# Yaris_speed_door_lock.net
KiCad netlist of a schematic drawn in EAGLE
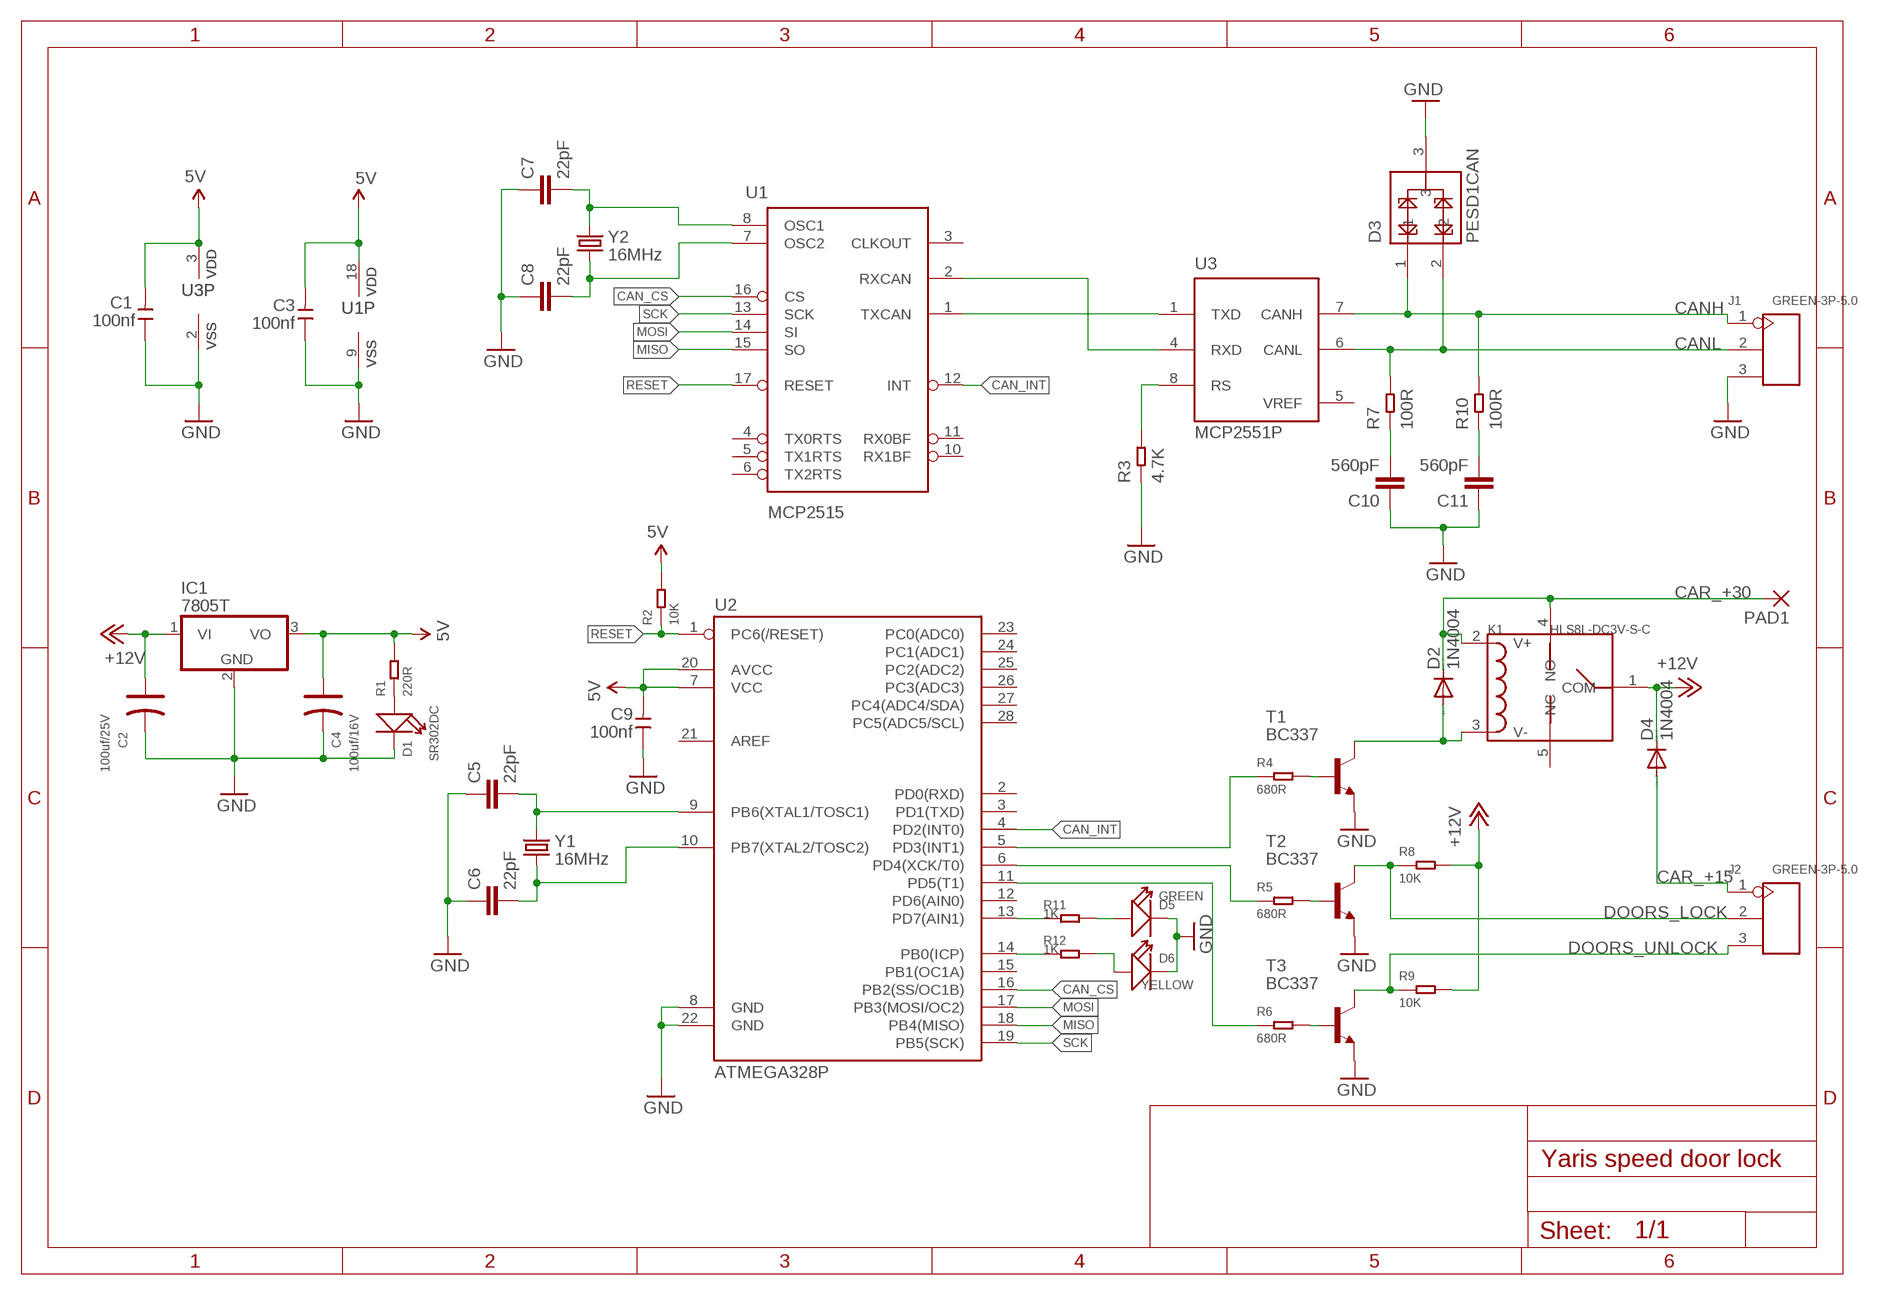
[diagram p0: schematic, sheet 1]

(export (version "E")
  (design (tool "Eeschema 10.0.6"))
  (components
    (comp (ref "C1")
      (value "100nf")
      (footprint "eagle-import:CERAMIC-2.54")
      (fields (field (name "MPN") "CC1-F5SL2A101KSPW"))
      (libsource (lib "eagle-import") (part "DIP-CERAMIC-DISC-100NF-50V-Y5V(D5.0MM)"))
    )
    (comp (ref "C2")
      (value "100uf/25V")
      (footprint "eagle-import:PC-D5.3MM")
      (fields (field (name "MPN") "KS 100uF/16V"))
      (libsource (lib "eagle-import") (part "DIP-ALUMINUM-100UF-16V(D5-H7MM)"))
    )
    (comp (ref "C3")
      (value "100nf")
      (footprint "eagle-import:CERAMIC-2.54")
      (fields (field (name "MPN") "CC1-F5SL2A101KSPW"))
      (libsource (lib "eagle-import") (part "DIP-CERAMIC-DISC-100NF-50V-Y5V(D5.0MM)"))
    )
    (comp (ref "C4")
      (value "100uf/16V")
      (footprint "eagle-import:PC-D5.3MM")
      (fields (field (name "MPN") "KS 100uF/16V"))
      (libsource (lib "eagle-import") (part "DIP-ALUMINUM-100UF-16V(D5-H7MM)"))
    )
    (comp (ref "C5")
      (value "22pF")
      (footprint "eagle-import:CAP-PTH-2.54")
      (libsource (lib "eagle-import") (part "22PF-PTH-2.54MM-200V-5%"))
    )
    (comp (ref "C6")
      (value "22pF")
      (footprint "eagle-import:CAP-PTH-2.54")
      (libsource (lib "eagle-import") (part "22PF-PTH-2.54MM-200V-5%"))
    )
    (comp (ref "C7")
      (value "22pF")
      (footprint "eagle-import:CAP-PTH-2.54")
      (libsource (lib "eagle-import") (part "22PF-PTH-2.54MM-200V-5%"))
    )
    (comp (ref "C8")
      (value "22pF")
      (footprint "eagle-import:CAP-PTH-2.54")
      (libsource (lib "eagle-import") (part "22PF-PTH-2.54MM-200V-5%"))
    )
    (comp (ref "C9")
      (value "100nf")
      (footprint "eagle-import:CERAMIC-2.54")
      (fields (field (name "MPN") "CC1-F5SL2A101KSPW"))
      (libsource (lib "eagle-import") (part "DIP-CERAMIC-DISC-100NF-50V-Y5V(D5.0MM)"))
    )
    (comp (ref "C10")
      (value "560pF")
      (footprint "eagle-import:0603-CAP")
      (libsource (lib "eagle-import") (part "560PF-50V-5%(0603)"))
    )
    (comp (ref "C11")
      (value "560pF")
      (footprint "eagle-import:0603-CAP")
      (libsource (lib "eagle-import") (part "560PF-50V-5%(0603)"))
    )
    (comp (ref "D1")
      (value "SR302DC")
      (footprint "eagle-import:LED2-2.54-D3.0MM")
      (libsource (lib "eagle-import") (part "DIP-LED-RED-RED(2P-D3MM)"))
    )
    (comp (ref "D2")
      (value "1N4004")
      (footprint "eagle-import:DO41-10")
      (libsource (lib "eagle-import") (part "1N4004"))
    )
    (comp (ref "D3")
      (value "PESD1CAN")
      (footprint "eagle-import:SOT23-3")
      (libsource (lib "eagle-import") (part "PESD1CAN"))
    )
    (comp (ref "D4")
      (value "1N4004")
      (footprint "eagle-import:DO41-10")
      (libsource (lib "eagle-import") (part "1N4004"))
    )
    (comp (ref "D5")
      (value "GREEN")
      (footprint "eagle-import:LED2-2.54-D3.0MM")
      (fields (field (name "MPN") "CX-G302DC"))
      (libsource (lib "eagle-import") (part "DIP-LED-GREEN-GREEN(2P-D3MM)"))
    )
    (comp (ref "D6")
      (value "YELLOW")
      (footprint "eagle-import:LED2-2.54-D3.0MM")
      (fields (field (name "MPN") "CX-G302DC"))
      (libsource (lib "eagle-import") (part "DIP-LED-GREEN-GREEN(2P-D3MM)"))
    )
    (comp (ref "IC1")
      (value "7805T")
      (footprint "eagle-import:TO220H")
      (libsource (lib "eagle-import") (part "78T05"))
    )
    (comp (ref "J1")
      (value "GREEN-3P-5.0")
      (footprint "eagle-import:H3-5.0-15.5X8.0MM")
      (libsource (lib "eagle-import") (part "SCREW-TERMINAL-GREEN(3P-5.0)"))
    )
    (comp (ref "J2")
      (value "GREEN-3P-5.0")
      (footprint "eagle-import:H3-5.0-15.5X8.0MM")
      (libsource (lib "eagle-import") (part "SCREW-TERMINAL-GREEN(3P-5.0)"))
    )
    (comp (ref "K1")
      (value "HLS8L-DC3V-S-C")
      (footprint "eagle-import:REY5-19.0X15.0X15.0MM")
      (libsource (lib "eagle-import") (part "RELAY-HLS8L-DC3V-S-C(5P-19X15MM)"))
    )
    (comp (ref "PAD1")
      (value "2,15/1,0")
      (footprint "eagle-import:2,15_1,0")
      (libsource (lib "eagle-import") (part "2,15/1,0"))
    )
    (comp (ref "R1")
      (value "220R")
      (footprint "eagle-import:PR-D2.3XL6.5MM")
      (fields (field (name "MPN") "FHCFR-1/4W-221J"))
      (libsource (lib "eagle-import") (part "DIP-RES-220R-5%-1/4W(PR-D2.3XL6.5MM)"))
    )
    (comp (ref "R2")
      (value "10K")
      (footprint "eagle-import:PR-D2.3XL6.5MM")
      (fields (field (name "MPN") "FHCFR-1/4W-103J"))
      (libsource (lib "eagle-import") (part "DIP-RES-10K-5%-1/4W(PR-D2.3XL6.5MM)"))
    )
    (comp (ref "R3")
      (value "4.7K")
      (footprint "eagle-import:PR-D2.3XL6.5MM")
      (fields (field (name "MPN") "FHCFR-1/4W-472J"))
      (libsource (lib "eagle-import") (part "DIP-RES-4.7K-5%-1/4W(PR-D2.3XL6.5MM)"))
    )
    (comp (ref "R4")
      (value "680R")
      (footprint "eagle-import:PR-D2.3XL6.5MM")
      (fields (field (name "MPN") "FHCFR-1/4W-681J"))
      (libsource (lib "eagle-import") (part "DIP-RES-680R-5%-1/4W(PR-D2.3XL6.5MM)"))
    )
    (comp (ref "R5")
      (value "680R")
      (footprint "eagle-import:PR-D2.3XL6.5MM")
      (fields (field (name "MPN") "FHCFR-1/4W-681J"))
      (libsource (lib "eagle-import") (part "DIP-RES-680R-5%-1/4W(PR-D2.3XL6.5MM)"))
    )
    (comp (ref "R6")
      (value "680R")
      (footprint "eagle-import:PR-D2.3XL6.5MM")
      (fields (field (name "MPN") "FHCFR-1/4W-681J"))
      (libsource (lib "eagle-import") (part "DIP-RES-680R-5%-1/4W(PR-D2.3XL6.5MM)"))
    )
    (comp (ref "R7")
      (value "100R")
      (footprint "eagle-import:PR-D2.3XL6.5MM")
      (fields (field (name "MPN") "FHCFR-1/4W-101J"))
      (libsource (lib "eagle-import") (part "DIP-RES-100R-5%-1/4W(PR-D2.3XL6.5MM)"))
    )
    (comp (ref "R8")
      (value "10K")
      (footprint "eagle-import:PR-D2.3XL6.5MM")
      (fields (field (name "MPN") "FHCFR-1/4W-103J"))
      (libsource (lib "eagle-import") (part "DIP-RES-10K-5%-1/4W(PR-D2.3XL6.5MM)"))
    )
    (comp (ref "R9")
      (value "10K")
      (footprint "eagle-import:PR-D2.3XL6.5MM")
      (fields (field (name "MPN") "FHCFR-1/4W-103J"))
      (libsource (lib "eagle-import") (part "DIP-RES-10K-5%-1/4W(PR-D2.3XL6.5MM)"))
    )
    (comp (ref "R10")
      (value "100R")
      (footprint "eagle-import:PR-D2.3XL6.5MM")
      (fields (field (name "MPN") "FHCFR-1/4W-101J"))
      (libsource (lib "eagle-import") (part "DIP-RES-100R-5%-1/4W(PR-D2.3XL6.5MM)"))
    )
    (comp (ref "R11")
      (value "1K")
      (footprint "eagle-import:PR-D2.3XL6.5MM")
      (fields (field (name "MPN") "FHCFR-1/4W-102J"))
      (libsource (lib "eagle-import") (part "DIP-RES-1K-5%-1/4W(PR-D2.3XL6.5MM)"))
    )
    (comp (ref "R12")
      (value "1K")
      (footprint "eagle-import:PR-D2.3XL6.5MM")
      (fields (field (name "MPN") "FHCFR-1/4W-102J"))
      (libsource (lib "eagle-import") (part "DIP-RES-1K-5%-1/4W(PR-D2.3XL6.5MM)"))
    )
    (comp (ref "T1")
      (value "BC337")
      (footprint "eagle-import:TO92")
      (libsource (lib "eagle-import") (part "BC337"))
    )
    (comp (ref "T2")
      (value "BC337")
      (footprint "eagle-import:TO92")
      (libsource (lib "eagle-import") (part "BC337"))
    )
    (comp (ref "T3")
      (value "BC337")
      (footprint "eagle-import:TO92")
      (libsource (lib "eagle-import") (part "BC337"))
    )
    (comp (ref "U1")
      (value "MCP2515")
      (footprint "eagle-import:SO-18W")
      (libsource (lib "eagle-import") (part "MCP2510SO"))
    )
    (comp (ref "U2")
      (value "ATMEGA328P")
      (footprint "eagle-import:DIP28")
      (libsource (lib "eagle-import") (part "ATMEGA328P_PDIP"))
    )
    (comp (ref "U3")
      (value "MCP2551P")
      (footprint "eagle-import:DIL8")
      (libsource (lib "eagle-import") (part "MCP2551P"))
    )
    (comp (ref "Y1")
      (value "16MHz")
      (footprint "eagle-import:HC49US")
      (libsource (lib "eagle-import") (part "CRYSTALHC49US"))
    )
    (comp (ref "Y2")
      (value "16MHz")
      (footprint "eagle-import:HC49US")
      (libsource (lib "eagle-import") (part "CRYSTALHC49US"))
    )
  )
  (nets
    (net (code "1") (name "+12V") (class "Default")
      (node (ref "C2") (pin "+") (pinfunction "+_+") (pintype "passive"))
      (node (ref "D4") (pin "C") (pinfunction "C_C") (pintype "passive"))
      (node (ref "IC1") (pin "1") (pinfunction "VI_1") (pintype "input"))
      (node (ref "K1") (pin "1") (pinfunction "COM_1") (pintype "bidirectional"))
      (node (ref "R8") (pin "2") (pinfunction "2_2") (pintype "passive"))
      (node (ref "R9") (pin "2") (pinfunction "2_2") (pintype "passive"))
    )
    (net (code "2") (name "/CANH") (class "Default")
      (node (ref "D3") (pin "1") (pinfunction "1_1") (pintype "bidirectional"))
      (node (ref "J1") (pin "1") (pinfunction "P$1_1") (pintype "bidirectional"))
      (node (ref "R10") (pin "2") (pinfunction "2_2") (pintype "passive"))
      (node (ref "U3") (pin "7") (pinfunction "CANH_7") (pintype "bidirectional"))
    )
    (net (code "3") (name "/CANL") (class "Default")
      (node (ref "D3") (pin "2") (pinfunction "2_2") (pintype "bidirectional"))
      (node (ref "J1") (pin "2") (pinfunction "P$2_2") (pintype "bidirectional"))
      (node (ref "R7") (pin "2") (pinfunction "2_2") (pintype "passive"))
      (node (ref "U3") (pin "6") (pinfunction "CANL_6") (pintype "bidirectional"))
    )
    (net (code "4") (name "/CAR_+15") (class "Default")
      (node (ref "D4") (pin "A") (pinfunction "A_A") (pintype "passive"))
      (node (ref "J2") (pin "1") (pinfunction "P$1_1") (pintype "bidirectional"))
    )
    (net (code "5") (name "/CAR_+30") (class "Default")
      (node (ref "D2") (pin "C") (pinfunction "C_C") (pintype "passive"))
      (node (ref "K1") (pin "2") (pinfunction "V+_2") (pintype "bidirectional"))
      (node (ref "K1") (pin "4") (pinfunction "NO_4") (pintype "bidirectional"))
      (node (ref "PAD1") (pin "1") (pinfunction "P_1") (pintype "passive"))
    )
    (net (code "6") (name "/DOORS_LOCK") (class "Default")
      (node (ref "J2") (pin "2") (pinfunction "P$2_2") (pintype "bidirectional"))
      (node (ref "R8") (pin "1") (pinfunction "1_1") (pintype "passive"))
      (node (ref "T2") (pin "3") (pinfunction "C_3") (pintype "passive"))
    )
    (net (code "7") (name "/DOORS_UNLOCK") (class "Default")
      (node (ref "J2") (pin "3") (pinfunction "P$3_3") (pintype "bidirectional"))
      (node (ref "R9") (pin "1") (pinfunction "1_1") (pintype "passive"))
      (node (ref "T3") (pin "3") (pinfunction "C_3") (pintype "passive"))
    )
    (net (code "8") (name "/VREF") (class "Default")
      (node (ref "U3") (pin "5") (pinfunction "VREF_5") (pintype "power_in"))
    )
    (net (code "9") (name "5V") (class "Default")
      (node (ref "C1") (pin "2") (pinfunction "2_2") (pintype "passive"))
      (node (ref "C3") (pin "2") (pinfunction "2_2") (pintype "passive"))
      (node (ref "C4") (pin "+") (pinfunction "+_+") (pintype "passive"))
      (node (ref "C9") (pin "2") (pinfunction "2_2") (pintype "passive"))
      (node (ref "IC1") (pin "3") (pinfunction "VO_3") (pintype "passive"))
      (node (ref "R1") (pin "2") (pinfunction "2_2") (pintype "passive"))
      (node (ref "R2") (pin "2") (pinfunction "2_2") (pintype "passive"))
      (node (ref "U1") (pin "18") (pinfunction "VDD_18") (pintype "power_in"))
      (node (ref "U2") (pin "20") (pinfunction "AVCC_20") (pintype "bidirectional"))
      (node (ref "U2") (pin "7") (pinfunction "VCC_7") (pintype "bidirectional"))
      (node (ref "U3") (pin "3") (pinfunction "VDD_3") (pintype "power_in"))
    )
    (net (code "10") (name "CAN_CS") (class "Default")
      (node (ref "U1") (pin "16") (pinfunction "CS_16") (pintype "input"))
      (node (ref "U2") (pin "16") (pinfunction "PB2(SS/OC1B)_16") (pintype "bidirectional"))
    )
    (net (code "11") (name "CAN_INT") (class "Default")
      (node (ref "U1") (pin "12") (pinfunction "INT_12") (pintype "output"))
      (node (ref "U2") (pin "4") (pinfunction "PD2(INT0)_4") (pintype "bidirectional"))
    )
    (net (code "12") (name "GND") (class "Default")
      (node (ref "C1") (pin "1") (pinfunction "1_1") (pintype "passive"))
      (node (ref "C10") (pin "1") (pinfunction "1_1") (pintype "passive"))
      (node (ref "C11") (pin "1") (pinfunction "1_1") (pintype "passive"))
      (node (ref "C2") (pin "-") (pinfunction "-_-") (pintype "passive"))
      (node (ref "C3") (pin "1") (pinfunction "1_1") (pintype "passive"))
      (node (ref "C4") (pin "-") (pinfunction "-_-") (pintype "passive"))
      (node (ref "C5") (pin "1") (pinfunction "1_1") (pintype "passive"))
      (node (ref "C6") (pin "1") (pinfunction "1_1") (pintype "passive"))
      (node (ref "C7") (pin "1") (pinfunction "1_1") (pintype "passive"))
      (node (ref "C8") (pin "1") (pinfunction "1_1") (pintype "passive"))
      (node (ref "C9") (pin "1") (pinfunction "1_1") (pintype "passive"))
      (node (ref "D1") (pin "K") (pinfunction "-_K") (pintype "passive"))
      (node (ref "D3") (pin "3") (pinfunction "3_3") (pintype "bidirectional"))
      (node (ref "D5") (pin "K") (pinfunction "-_K") (pintype "passive"))
      (node (ref "D6") (pin "K") (pinfunction "-_K") (pintype "passive"))
      (node (ref "IC1") (pin "2") (pinfunction "GND_2") (pintype "passive"))
      (node (ref "J1") (pin "3") (pinfunction "P$3_3") (pintype "bidirectional"))
      (node (ref "R3") (pin "1") (pinfunction "1_1") (pintype "passive"))
      (node (ref "T1") (pin "1") (pinfunction "E_1") (pintype "passive"))
      (node (ref "T2") (pin "1") (pinfunction "E_1") (pintype "passive"))
      (node (ref "T3") (pin "1") (pinfunction "E_1") (pintype "passive"))
      (node (ref "U1") (pin "9") (pinfunction "VSS_9") (pintype "power_in"))
      (node (ref "U2") (pin "22") (pinfunction "GND_22") (pintype "bidirectional"))
      (node (ref "U2") (pin "8") (pinfunction "GND_8") (pintype "bidirectional"))
      (node (ref "U3") (pin "2") (pinfunction "VSS_2") (pintype "power_in"))
    )
    (net (code "13") (name "MISO") (class "Default")
      (node (ref "U1") (pin "15") (pinfunction "SO_15") (pintype "output"))
      (node (ref "U2") (pin "18") (pinfunction "PB4(MISO)_18") (pintype "bidirectional"))
    )
    (net (code "14") (name "MOSI") (class "Default")
      (node (ref "U1") (pin "14") (pinfunction "SI_14") (pintype "input"))
      (node (ref "U2") (pin "17") (pinfunction "PB3(MOSI/OC2)_17") (pintype "bidirectional"))
    )
    (net (code "15") (name "Net-(C10-Pad2)") (class "Default")
      (node (ref "C10") (pin "2") (pinfunction "2_2") (pintype "passive"))
      (node (ref "R7") (pin "1") (pinfunction "1_1") (pintype "passive"))
    )
    (net (code "16") (name "Net-(C11-Pad2)") (class "Default")
      (node (ref "C11") (pin "2") (pinfunction "2_2") (pintype "passive"))
      (node (ref "R10") (pin "1") (pinfunction "1_1") (pintype "passive"))
    )
    (net (code "17") (name "Net-(D1-+)") (class "Default")
      (node (ref "D1") (pin "A") (pinfunction "+_A") (pintype "passive"))
      (node (ref "R1") (pin "1") (pinfunction "1_1") (pintype "passive"))
    )
    (net (code "18") (name "Net-(D5-+)") (class "Default")
      (node (ref "D5") (pin "A") (pinfunction "+_A") (pintype "passive"))
      (node (ref "R11") (pin "2") (pinfunction "2_2") (pintype "passive"))
    )
    (net (code "19") (name "Net-(D6-+)") (class "Default")
      (node (ref "D6") (pin "A") (pinfunction "+_A") (pintype "passive"))
      (node (ref "R12") (pin "2") (pinfunction "2_2") (pintype "passive"))
    )
    (net (code "20") (name "Net-(K1-V-)") (class "Default")
      (node (ref "D2") (pin "A") (pinfunction "A_A") (pintype "passive"))
      (node (ref "K1") (pin "3") (pinfunction "V-_3") (pintype "bidirectional"))
      (node (ref "T1") (pin "3") (pinfunction "C_3") (pintype "passive"))
    )
    (net (code "21") (name "Net-(T1-B)") (class "Default")
      (node (ref "R4") (pin "2") (pinfunction "2_2") (pintype "passive"))
      (node (ref "T1") (pin "2") (pinfunction "B_2") (pintype "passive"))
    )
    (net (code "22") (name "Net-(T2-B)") (class "Default")
      (node (ref "R5") (pin "2") (pinfunction "2_2") (pintype "passive"))
      (node (ref "T2") (pin "2") (pinfunction "B_2") (pintype "passive"))
    )
    (net (code "23") (name "Net-(T3-B)") (class "Default")
      (node (ref "R6") (pin "2") (pinfunction "2_2") (pintype "passive"))
      (node (ref "T3") (pin "2") (pinfunction "B_2") (pintype "passive"))
    )
    (net (code "24") (name "Net-(U1A-OSC1)") (class "Default")
      (node (ref "C7") (pin "2") (pinfunction "2_2") (pintype "passive"))
      (node (ref "U1") (pin "8") (pinfunction "OSC1_8") (pintype "input"))
      (node (ref "Y2") (pin "2") (pinfunction "2_2") (pintype "passive"))
    )
    (net (code "25") (name "Net-(U1A-OSC2)") (class "Default")
      (node (ref "C8") (pin "2") (pinfunction "2_2") (pintype "passive"))
      (node (ref "U1") (pin "7") (pinfunction "OSC2_7") (pintype "output"))
      (node (ref "Y2") (pin "1") (pinfunction "1_1") (pintype "passive"))
    )
    (net (code "26") (name "Net-(U1A-RXCAN)") (class "Default")
      (node (ref "U1") (pin "2") (pinfunction "RXCAN_2") (pintype "input"))
      (node (ref "U3") (pin "4") (pinfunction "RXD_4") (pintype "output"))
    )
    (net (code "27") (name "Net-(U1A-TXCAN)") (class "Default")
      (node (ref "U1") (pin "1") (pinfunction "TXCAN_1") (pintype "output"))
      (node (ref "U3") (pin "1") (pinfunction "TXD_1") (pintype "input"))
    )
    (net (code "28") (name "Net-(U2-PB0(ICP))") (class "Default")
      (node (ref "R12") (pin "1") (pinfunction "1_1") (pintype "passive"))
      (node (ref "U2") (pin "14") (pinfunction "PB0(ICP)_14") (pintype "bidirectional"))
    )
    (net (code "29") (name "Net-(U2-PB6(XTAL1{slash}TOSC1))") (class "Default")
      (node (ref "C5") (pin "2") (pinfunction "2_2") (pintype "passive"))
      (node (ref "U2") (pin "9") (pinfunction "PB6(XTAL1/TOSC1)_9") (pintype "bidirectional"))
      (node (ref "Y1") (pin "2") (pinfunction "2_2") (pintype "passive"))
    )
    (net (code "30") (name "Net-(U2-PB7(XTAL2{slash}TOSC2))") (class "Default")
      (node (ref "C6") (pin "2") (pinfunction "2_2") (pintype "passive"))
      (node (ref "U2") (pin "10") (pinfunction "PB7(XTAL2/TOSC2)_10") (pintype "bidirectional"))
      (node (ref "Y1") (pin "1") (pinfunction "1_1") (pintype "passive"))
    )
    (net (code "31") (name "Net-(U2-PD3(INT1))") (class "Default")
      (node (ref "R4") (pin "1") (pinfunction "1_1") (pintype "passive"))
      (node (ref "U2") (pin "5") (pinfunction "PD3(INT1)_5") (pintype "bidirectional"))
    )
    (net (code "32") (name "Net-(U2-PD4(XCK{slash}T0))") (class "Default")
      (node (ref "R5") (pin "1") (pinfunction "1_1") (pintype "passive"))
      (node (ref "U2") (pin "6") (pinfunction "PD4(XCK/T0)_6") (pintype "bidirectional"))
    )
    (net (code "33") (name "Net-(U2-PD5(T1))") (class "Default")
      (node (ref "R6") (pin "1") (pinfunction "1_1") (pintype "passive"))
      (node (ref "U2") (pin "11") (pinfunction "PD5(T1)_11") (pintype "bidirectional"))
    )
    (net (code "34") (name "Net-(U2-PD7(AIN1))") (class "Default")
      (node (ref "R11") (pin "1") (pinfunction "1_1") (pintype "passive"))
      (node (ref "U2") (pin "13") (pinfunction "PD7(AIN1)_13") (pintype "bidirectional"))
    )
    (net (code "35") (name "Net-(U3A-RS)") (class "Default")
      (node (ref "R3") (pin "2") (pinfunction "2_2") (pintype "passive"))
      (node (ref "U3") (pin "8") (pinfunction "RS_8") (pintype "input"))
    )
    (net (code "36") (name "RESET") (class "Default")
      (node (ref "R2") (pin "1") (pinfunction "1_1") (pintype "passive"))
      (node (ref "U1") (pin "17") (pinfunction "RESET_17") (pintype "input"))
      (node (ref "U2") (pin "1") (pinfunction "PC6(/RESET)_1") (pintype "bidirectional"))
    )
    (net (code "37") (name "SCK") (class "Default")
      (node (ref "U1") (pin "13") (pinfunction "SCK_13") (pintype "input"))
      (node (ref "U2") (pin "19") (pinfunction "PB5(SCK)_19") (pintype "bidirectional"))
    )
    (net (code "38") (name "unconnected-(K1-NC-Pad5)") (class "Default")
      (node (ref "K1") (pin "5") (pinfunction "NC_5") (pintype "bidirectional"))
    )
    (net (code "39") (name "unconnected-(U1A-CLKOUT-Pad3)") (class "Default")
      (node (ref "U1") (pin "3") (pinfunction "CLKOUT_3") (pintype "output"))
    )
    (net (code "40") (name "unconnected-(U1A-RX0BF-Pad11)") (class "Default")
      (node (ref "U1") (pin "11") (pinfunction "RX0BF_11") (pintype "output"))
    )
    (net (code "41") (name "unconnected-(U1A-RX1BF-Pad10)") (class "Default")
      (node (ref "U1") (pin "10") (pinfunction "RX1BF_10") (pintype "output"))
    )
    (net (code "42") (name "unconnected-(U1A-TX0RTS-Pad4)") (class "Default")
      (node (ref "U1") (pin "4") (pinfunction "TX0RTS_4") (pintype "input"))
    )
    (net (code "43") (name "unconnected-(U1A-TX1RTS-Pad5)") (class "Default")
      (node (ref "U1") (pin "5") (pinfunction "TX1RTS_5") (pintype "input"))
    )
    (net (code "44") (name "unconnected-(U1A-TX2RTS-Pad6)") (class "Default")
      (node (ref "U1") (pin "6") (pinfunction "TX2RTS_6") (pintype "input"))
    )
    (net (code "45") (name "unconnected-(U2-AREF-Pad21)") (class "Default")
      (node (ref "U2") (pin "21") (pinfunction "AREF_21") (pintype "bidirectional"))
    )
    (net (code "46") (name "unconnected-(U2-PB1(OC1A)-Pad15)") (class "Default")
      (node (ref "U2") (pin "15") (pinfunction "PB1(OC1A)_15") (pintype "bidirectional"))
    )
    (net (code "47") (name "unconnected-(U2-PC0(ADC0)-Pad23)") (class "Default")
      (node (ref "U2") (pin "23") (pinfunction "PC0(ADC0)_23") (pintype "bidirectional"))
    )
    (net (code "48") (name "unconnected-(U2-PC1(ADC1)-Pad24)") (class "Default")
      (node (ref "U2") (pin "24") (pinfunction "PC1(ADC1)_24") (pintype "bidirectional"))
    )
    (net (code "49") (name "unconnected-(U2-PC2(ADC2)-Pad25)") (class "Default")
      (node (ref "U2") (pin "25") (pinfunction "PC2(ADC2)_25") (pintype "bidirectional"))
    )
    (net (code "50") (name "unconnected-(U2-PC3(ADC3)-Pad26)") (class "Default")
      (node (ref "U2") (pin "26") (pinfunction "PC3(ADC3)_26") (pintype "bidirectional"))
    )
    (net (code "51") (name "unconnected-(U2-PC4(ADC4{slash}SDA)-Pad27)") (class "Default")
      (node (ref "U2") (pin "27") (pinfunction "PC4(ADC4/SDA)_27") (pintype "bidirectional"))
    )
    (net (code "52") (name "unconnected-(U2-PC5(ADC5{slash}SCL)-Pad28)") (class "Default")
      (node (ref "U2") (pin "28") (pinfunction "PC5(ADC5/SCL)_28") (pintype "bidirectional"))
    )
    (net (code "53") (name "unconnected-(U2-PD0(RXD)-Pad2)") (class "Default")
      (node (ref "U2") (pin "2") (pinfunction "PD0(RXD)_2") (pintype "bidirectional"))
    )
    (net (code "54") (name "unconnected-(U2-PD1(TXD)-Pad3)") (class "Default")
      (node (ref "U2") (pin "3") (pinfunction "PD1(TXD)_3") (pintype "bidirectional"))
    )
    (net (code "55") (name "unconnected-(U2-PD6(AIN0)-Pad12)") (class "Default")
      (node (ref "U2") (pin "12") (pinfunction "PD6(AIN0)_12") (pintype "bidirectional"))
    )
  )
)
